# task1-3.net
KiCad netlist of a schematic drawn in EasyEDA Pro
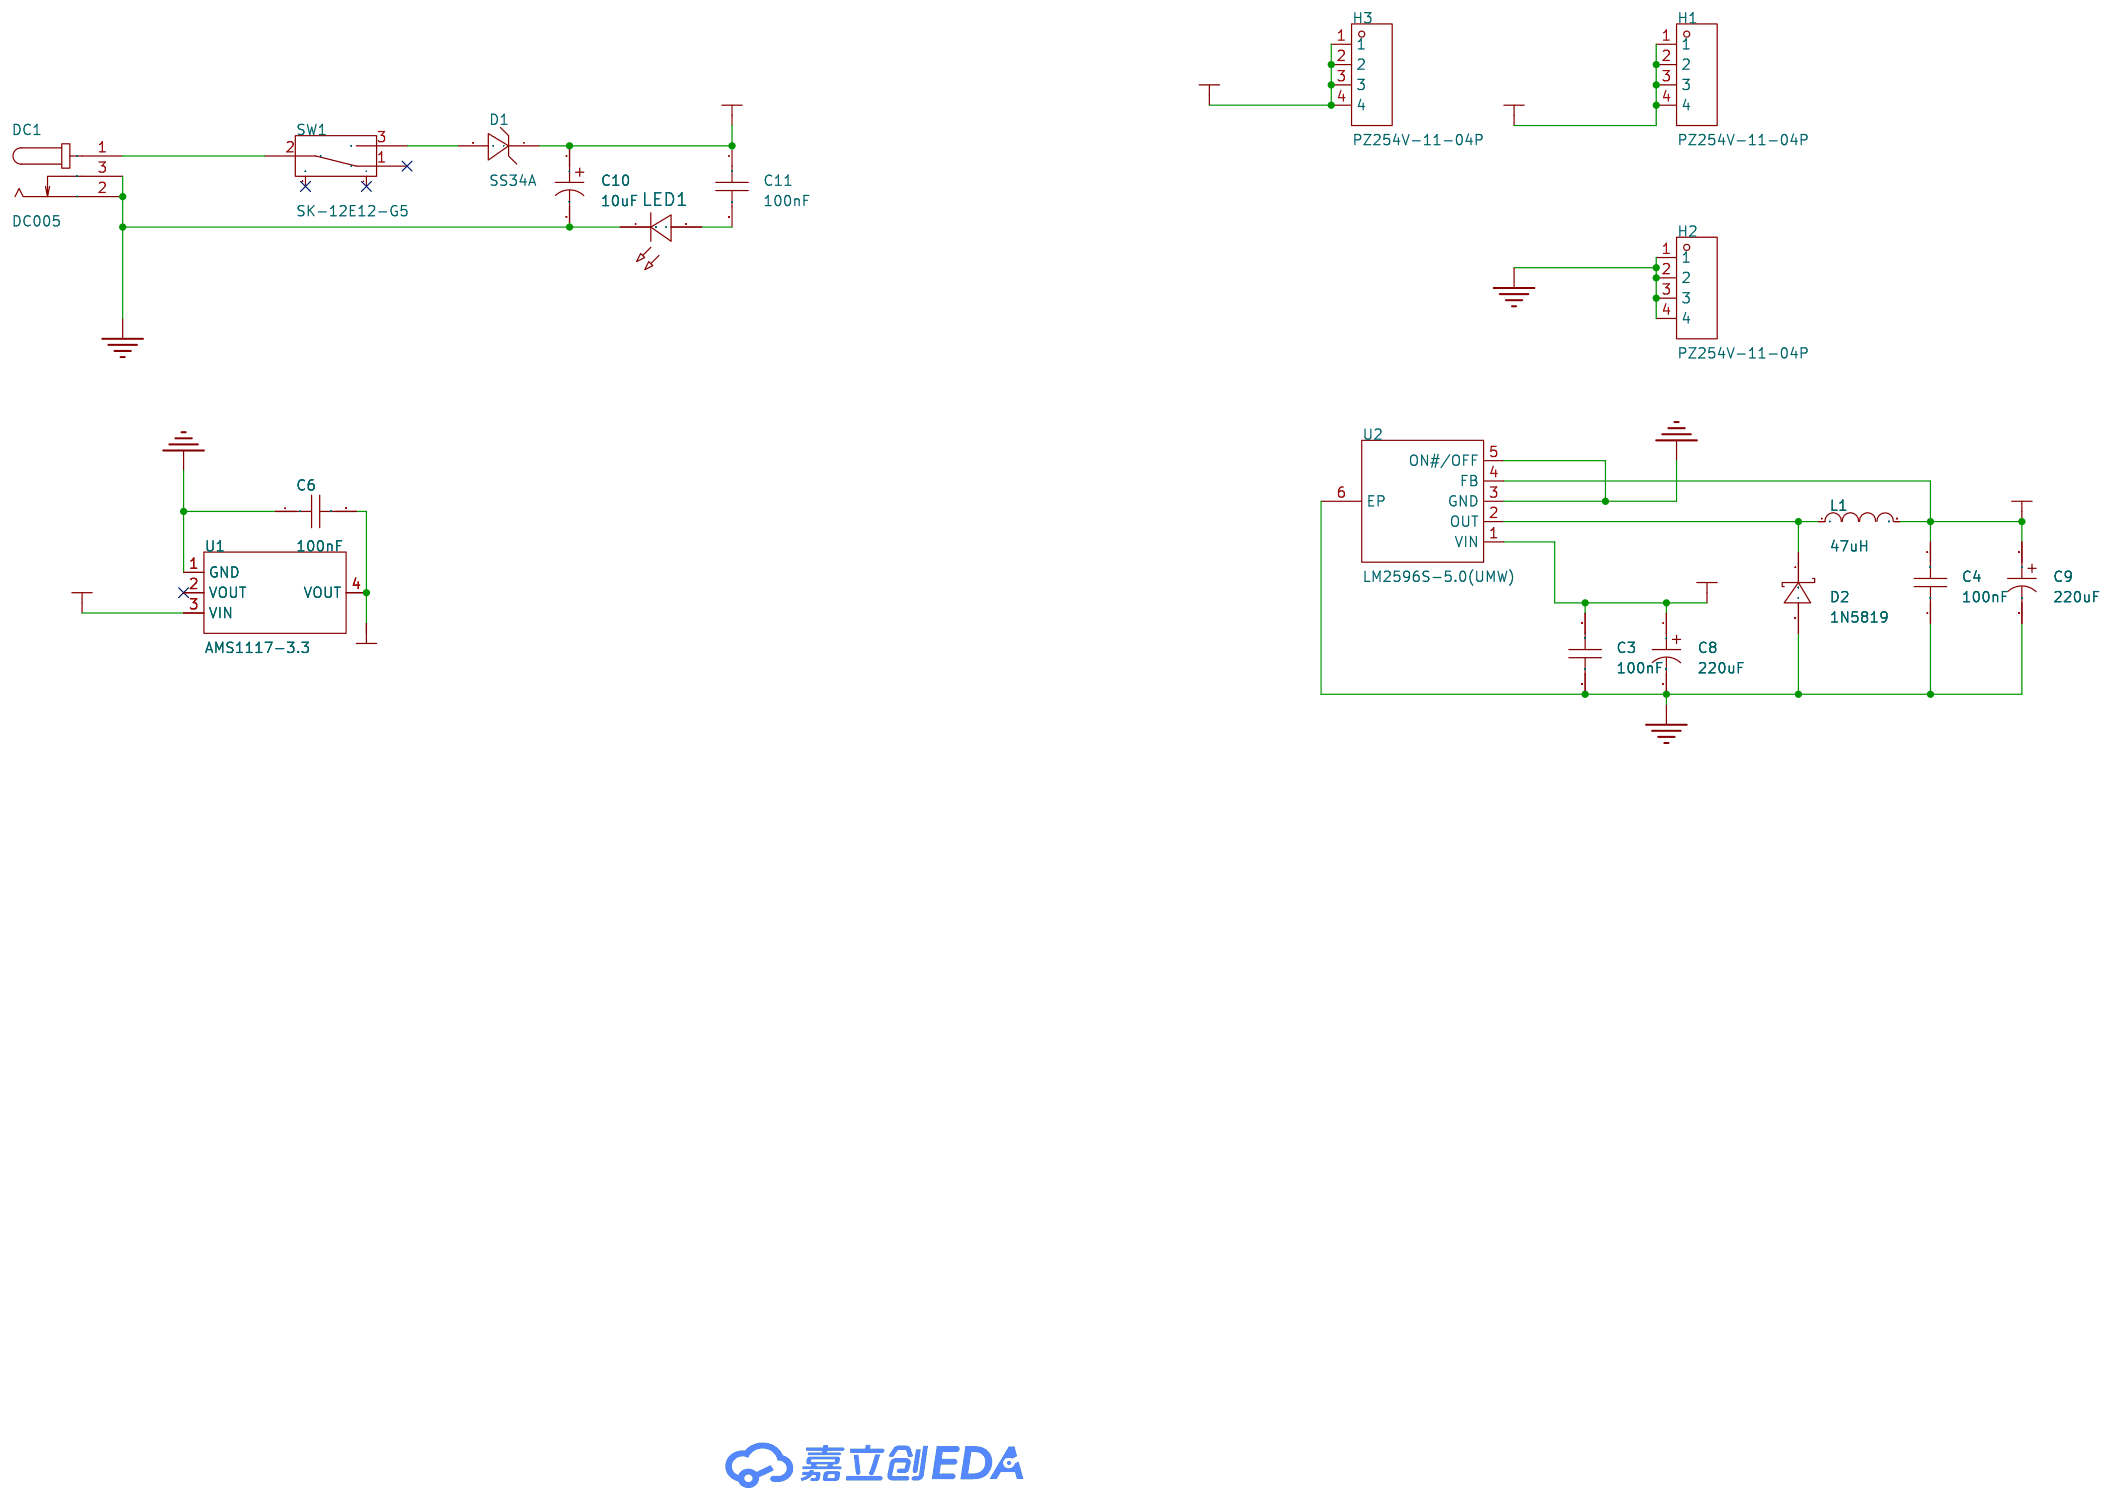
[diagram p0: schematic sheet]

(export (version "E")
  (design (tool "Eeschema 10.0.6"))
  (components
    (comp (ref "C3")
      (value "100nF")
      (footprint "easyedapro:C0603")
      (libsource (lib "easyedapro") (part "Capacitance"))
    )
    (comp (ref "C4")
      (value "100nF")
      (footprint "easyedapro:C0603")
      (libsource (lib "easyedapro") (part "Capacitance"))
    )
    (comp (ref "C6")
      (value "100nF")
      (footprint "easyedapro:C0603")
      (libsource (lib "easyedapro") (part "Capacitance"))
    )
    (comp (ref "C8")
      (value "220uF")
      (footprint "easyedapro:CAP-TH_BD8.0-P3.50-D0.5-FD")
      (description "容值:220uF;精度:±20%;额定电压:35V;")
      (fields (field (name "Manufacturer Part") "ERA35V220M8X12") (field (name "Manufacturer") "JIERR(捷而瑞)"))
      (libsource (lib "easyedapro") (part "ERA35V220M8X12"))
    )
    (comp (ref "C9")
      (value "220uF")
      (footprint "easyedapro:CAP-TH_BD8.0-P3.50-D0.5-FD")
      (description "容值:220uF;精度:±20%;额定电压:35V;")
      (fields (field (name "Manufacturer Part") "ERA35V220M8X12") (field (name "Manufacturer") "JIERR(捷而瑞)"))
      (libsource (lib "easyedapro") (part "ERA35V220M8X12"))
    )
    (comp (ref "C10")
      (value "10uF")
      (footprint "easyedapro:CAP-TH_BD10.0-P5.00-D0.6-FD_1")
      (description "容值:10uF;精度:±20%;额定电压:450V;纹波电流:100mA@100kHz;等效串联电阻(ESR):9.45Ω@100kHz;")
      (fields (field (name "Manufacturer Part") "ERG450V10M10x16") (field (name "Manufacturer") "JIERR(捷而瑞)"))
      (libsource (lib "easyedapro") (part "ERG450V10M10X16"))
    )
    (comp (ref "C11")
      (value "100nF")
      (footprint "easyedapro:C0603")
      (libsource (lib "easyedapro") (part "Capacitance"))
    )
    (comp (ref "D1")
      (value "SS34A")
      (footprint "easyedapro:SMA_L4.4-W2.6-LS5.1-RD")
      (description "二极管配置:独立式;正向压降(Vf):500mV@3A;直流反向耐压(Vr):40V;整流电流:3A;")
      (fields (field (name "Manufacturer") "Hottech(合科泰)"))
      (libsource (lib "easyedapro") (part "SS34A_C2886580"))
    )
    (comp (ref "D2")
      (value "1N5819")
      (footprint "easyedapro:SMA_L4.4-W2.6-LS5.0-RD")
      (description "正向压降(Vf):500mV@1A;直流反向耐压(Vr):40V;整流电流:1A;")
      (fields (field (name "Manufacturer") "KEXIN(科信)"))
      (libsource (lib "easyedapro") (part "1N5819_C437199"))
    )
    (comp (ref "DC1")
      (value "DC005")
      (footprint "easyedapro:DC-IN-TH_DC005")
      (description "连接器类型:DC电源插座;安装方式:弯插;触点内径:2mm;触点外径:6.3mm;额定电流:500mA;额定电压:12V;工作温度:-30°C~+70°C;")
      (fields (field (name "Manufacturer") "SHOU HAN(首韩)"))
      (libsource (lib "easyedapro") (part "DC005_C431533"))
    )
    (comp (ref "H1")
      (value "PZ254V-11-04P")
      (footprint "easyedapro:HDR-TH_4P-P2.54-V-M")
      (fields (field (name "Manufacturer") "XFCN(兴飞)"))
      (libsource (lib "easyedapro") (part "PZ254V-11-04P_C2691448"))
    )
    (comp (ref "H2")
      (value "PZ254V-11-04P")
      (footprint "easyedapro:HDR-TH_4P-P2.54-V-M")
      (fields (field (name "Manufacturer") "XFCN(兴飞)"))
      (libsource (lib "easyedapro") (part "PZ254V-11-04P_C2691448"))
    )
    (comp (ref "H3")
      (value "PZ254V-11-04P")
      (footprint "easyedapro:HDR-TH_4P-P2.54-V-M")
      (fields (field (name "Manufacturer") "XFCN(兴飞)"))
      (libsource (lib "easyedapro") (part "PZ254V-11-04P_C2691448"))
    )
    (comp (ref "L1")
      (value "47uH")
      (footprint "easyedapro:L0603")
      (libsource (lib "easyedapro") (part "SDFL1608S100KTF"))
    )
    (comp (ref "LED1")
      (value "~")
      (footprint "easyedapro:LED_0603")
      (libsource (lib "easyedapro") (part "LED_R"))
    )
    (comp (ref "SW1")
      (value "SK-12E12-G5")
      (footprint "easyedapro:SW-TH_SK-12E12-G5")
      (description "电路结构:单刀双掷;安装方式:-;额定电流:-;额定电压:-;工作寿命:5千次;")
      (fields (field (name "Manufacturer") "韩国韩荣"))
      (libsource (lib "easyedapro") (part "SK-12E12-G5"))
    )
    (comp (ref "U1")
      (value "AMS1117-3.3")
      (footprint "easyedapro:SOT-223-3_L6.5-W3.4-P2.30-LS7.0-BR")
      (description "输出类型:固定;工作电压:16V;输出电压:3.3V;输出电流:1A;电源纹波抑制比(PSRR):72dB@(120Hz);输出极性:正极;")
      (fields (field (name "Manufacturer") "AMS"))
      (libsource (lib "easyedapro") (part "AMS1117-3.3"))
    )
    (comp (ref "U2")
      (value "LM2596S-5.0(UMW)")
      (footprint "easyedapro:TO-263-5_L10.2-W8.9-P1.70-BR")
      (description "功能类型:降压型;工作电压:7V~40V;输出电压:5V;输出电流:3A;输出类型:固定;")
      (fields (field (name "Manufacturer") "UMW(友台半导体)"))
      (libsource (lib "easyedapro") (part "LM2596S-5.0"))
    )
  )
  (nets
    (net (code "1") (name "3.3") (class "Default")
      (node (ref "C6") (pin "2") (pinfunction "2_2") (pintype "input"))
      (node (ref "H3") (pin "1") (pinfunction "1_1") (pintype "unspecified"))
      (node (ref "H3") (pin "2") (pinfunction "2_2") (pintype "unspecified"))
      (node (ref "H3") (pin "3") (pinfunction "3_3") (pintype "unspecified"))
      (node (ref "H3") (pin "4") (pinfunction "4_4") (pintype "unspecified"))
      (node (ref "U1") (pin "4") (pinfunction "VOUT_4") (pintype "unspecified"))
    )
    (net (code "2") (name "12V") (class "Default")
      (node (ref "C10") (pin "1") (pinfunction "1_1") (pintype "input"))
      (node (ref "C11") (pin "1") (pinfunction "1_1") (pintype "input"))
      (node (ref "C3") (pin "2") (pinfunction "2_2") (pintype "input"))
      (node (ref "C8") (pin "1") (pinfunction "1_1") (pintype "input"))
      (node (ref "D1") (pin "1") (pinfunction "1_1") (pintype "unspecified"))
      (node (ref "U1") (pin "3") (pinfunction "VIN_3") (pintype "unspecified"))
      (node (ref "U2") (pin "1") (pinfunction "VIN_1") (pintype "unspecified"))
    )
    (net (code "3") (name "GND") (class "Default")
      (node (ref "C10") (pin "2") (pinfunction "2_2") (pintype "input"))
      (node (ref "C3") (pin "1") (pinfunction "1_1") (pintype "input"))
      (node (ref "C4") (pin "1") (pinfunction "1_1") (pintype "input"))
      (node (ref "C6") (pin "1") (pinfunction "1_1") (pintype "input"))
      (node (ref "C8") (pin "2") (pinfunction "2_2") (pintype "input"))
      (node (ref "C9") (pin "2") (pinfunction "2_2") (pintype "input"))
      (node (ref "D2") (pin "2") (pinfunction "A_2") (pintype "unspecified"))
      (node (ref "DC1") (pin "2") (pinfunction "2_2") (pintype "unspecified"))
      (node (ref "DC1") (pin "3") (pinfunction "3_3") (pintype "unspecified"))
      (node (ref "H2") (pin "1") (pinfunction "1_1") (pintype "unspecified"))
      (node (ref "H2") (pin "2") (pinfunction "2_2") (pintype "unspecified"))
      (node (ref "H2") (pin "3") (pinfunction "3_3") (pintype "unspecified"))
      (node (ref "H2") (pin "4") (pinfunction "4_4") (pintype "unspecified"))
      (node (ref "LED1") (pin "1") (pinfunction "C_1") (pintype "input"))
      (node (ref "U1") (pin "1") (pinfunction "GND_1") (pintype "unspecified"))
      (node (ref "U2") (pin "3") (pinfunction "GND_3") (pintype "unspecified"))
      (node (ref "U2") (pin "5") (pinfunction "ON#/OFF_5") (pintype "unspecified"))
      (node (ref "U2") (pin "6") (pinfunction "EP_6") (pintype "unspecified"))
    )
    (net (code "4") (name "Net-(D1-Pad2)") (class "Default")
      (node (ref "D1") (pin "2") (pinfunction "2_2") (pintype "unspecified"))
      (node (ref "SW1") (pin "3") (pinfunction "3_3") (pintype "unspecified"))
    )
    (net (code "5") (name "Net-(D2-C)") (class "Default")
      (node (ref "D2") (pin "1") (pinfunction "C_1") (pintype "unspecified"))
      (node (ref "L1") (pin "1") (pinfunction "1_1") (pintype "unspecified"))
      (node (ref "U2") (pin "2") (pinfunction "OUT_2") (pintype "unspecified"))
    )
    (net (code "6") (name "Net-(DC1-Pad1)") (class "Default")
      (node (ref "DC1") (pin "1") (pinfunction "1_1") (pintype "unspecified"))
      (node (ref "SW1") (pin "2") (pinfunction "2_2") (pintype "unspecified"))
    )
    (net (code "7") (name "Net-(LED1-A)") (class "Default")
      (node (ref "C11") (pin "2") (pinfunction "2_2") (pintype "input"))
      (node (ref "LED1") (pin "2") (pinfunction "A_2") (pintype "input"))
    )
    (net (code "8") (name "VOUT") (class "Default")
      (node (ref "C4") (pin "2") (pinfunction "2_2") (pintype "input"))
      (node (ref "C9") (pin "1") (pinfunction "1_1") (pintype "input"))
      (node (ref "H1") (pin "1") (pinfunction "1_1") (pintype "unspecified"))
      (node (ref "H1") (pin "2") (pinfunction "2_2") (pintype "unspecified"))
      (node (ref "H1") (pin "3") (pinfunction "3_3") (pintype "unspecified"))
      (node (ref "H1") (pin "4") (pinfunction "4_4") (pintype "unspecified"))
      (node (ref "L1") (pin "2") (pinfunction "2_2") (pintype "unspecified"))
      (node (ref "U2") (pin "4") (pinfunction "FB_4") (pintype "unspecified"))
    )
    (net (code "9") (name "unconnected-(SW1-Pad1)") (class "Default")
      (node (ref "SW1") (pin "1") (pinfunction "1_1") (pintype "unspecified+no_connect"))
    )
    (net (code "10") (name "unconnected-(SW1-Pad4)") (class "Default")
      (node (ref "SW1") (pin "4") (pinfunction "4_4") (pintype "unspecified+no_connect"))
    )
    (net (code "11") (name "unconnected-(SW1-Pad5)") (class "Default")
      (node (ref "SW1") (pin "5") (pinfunction "5_5") (pintype "unspecified+no_connect"))
    )
    (net (code "12") (name "unconnected-(U1-VOUT-Pad2)") (class "Default")
      (node (ref "U1") (pin "2") (pinfunction "VOUT_2") (pintype "unspecified+no_connect"))
    )
  )
)
